# Eurorack_breadboard_PSU_ad.net
KiCad netlist of a schematic drawn in EAGLE
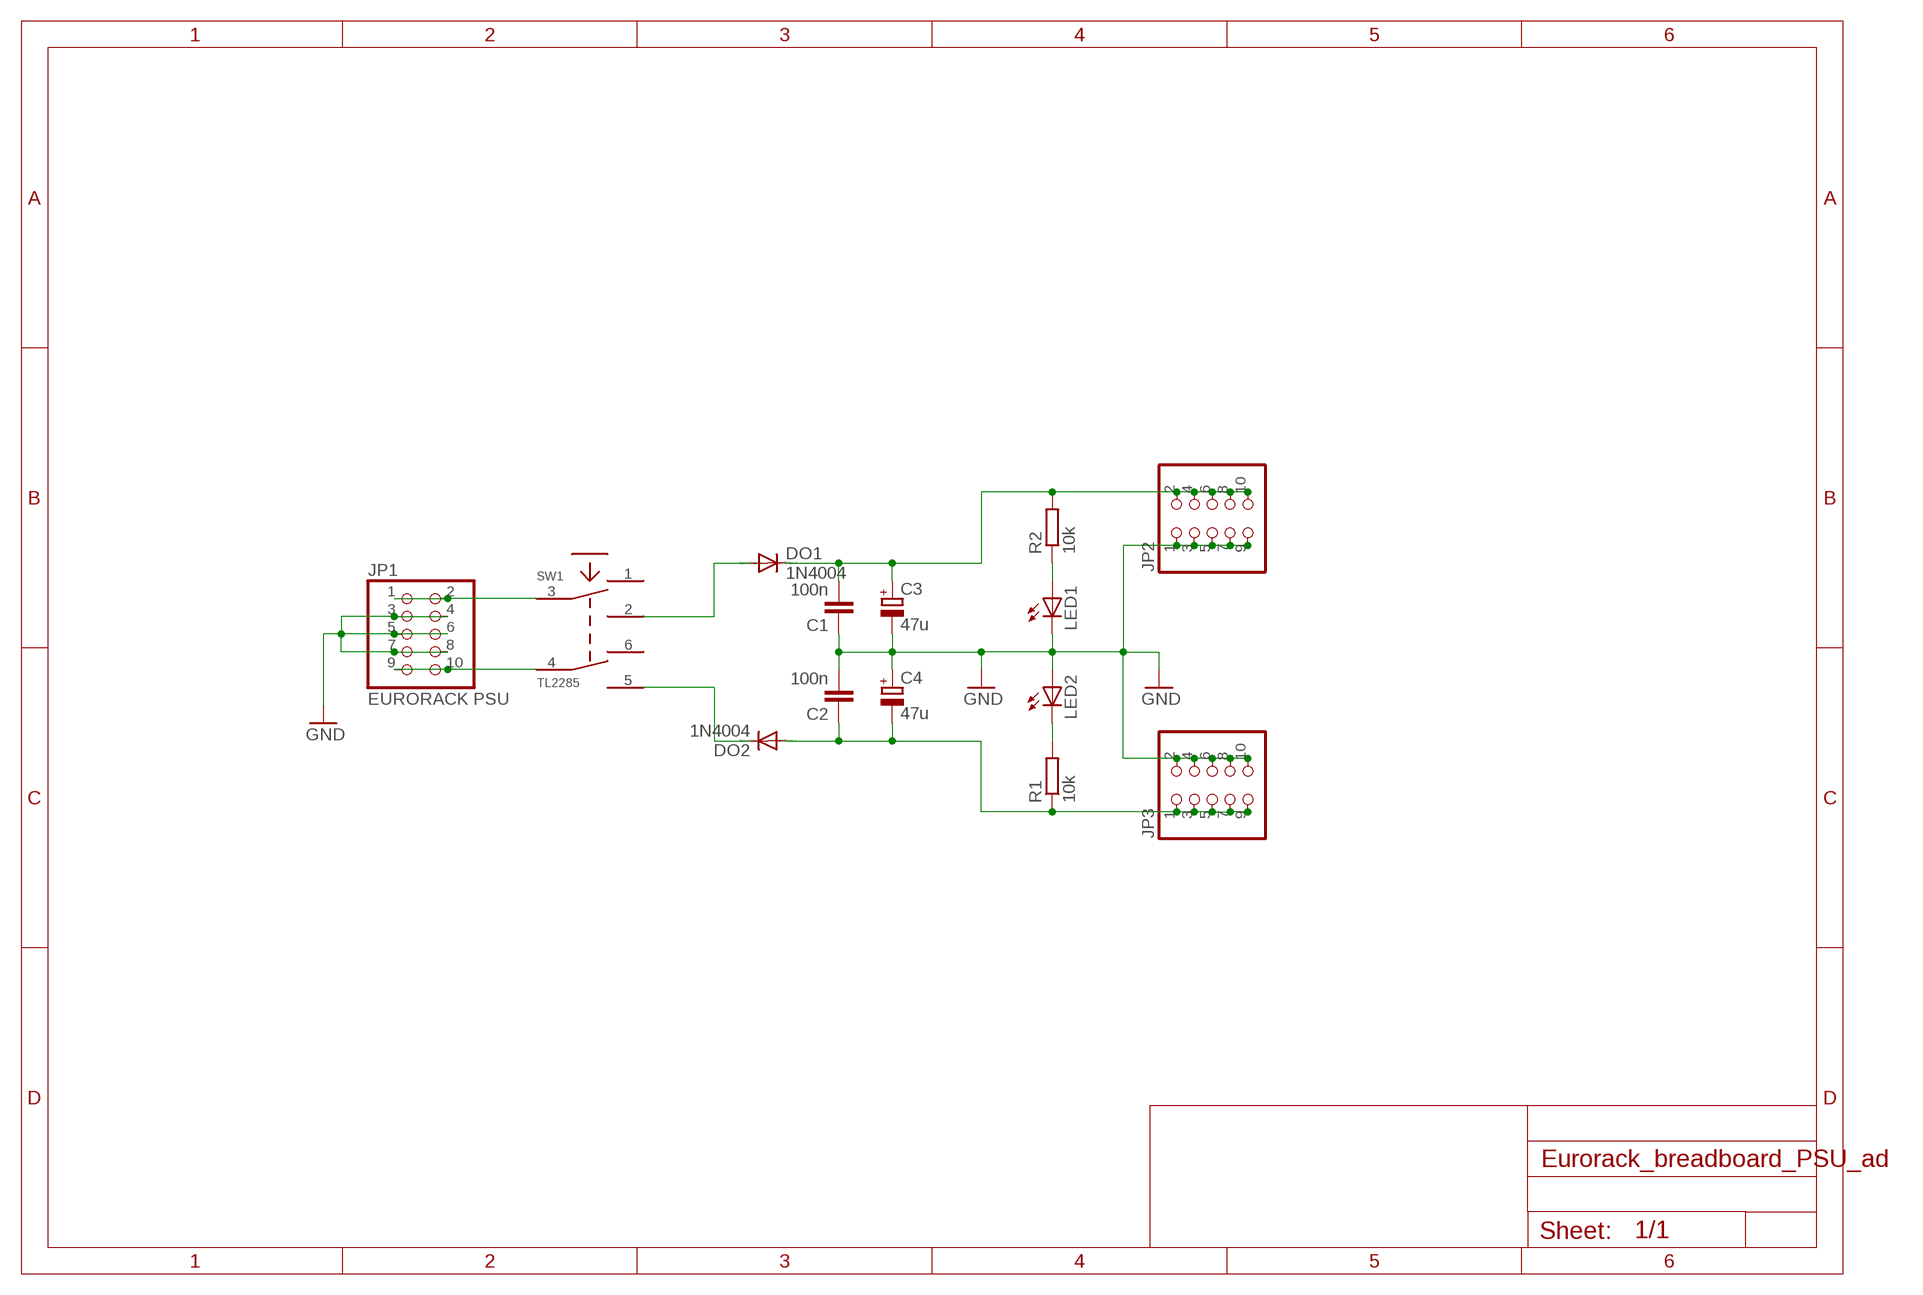
[diagram p0: schematic, sheet 1]

(export (version "E")
  (design (tool "Eeschema 10.0.6"))
  (components
    (comp (ref "C1")
      (value "100n")
      (footprint "eagle-import:C025-025X050")
      (libsource (lib "eagle-import") (part "C-EU025-025X050"))
    )
    (comp (ref "C2")
      (value "100n")
      (footprint "eagle-import:C025-025X050")
      (libsource (lib "eagle-import") (part "C-EU025-025X050"))
    )
    (comp (ref "C3")
      (value "47u")
      (footprint "eagle-import:E2,5-5")
      (libsource (lib "eagle-import") (part "CPOL-EUE2.5-5"))
    )
    (comp (ref "C4")
      (value "47u")
      (footprint "eagle-import:E2,5-5")
      (libsource (lib "eagle-import") (part "CPOL-EUE2.5-5"))
    )
    (comp (ref "DO1")
      (value "1N4004")
      (footprint "eagle-import:DO41-7")
      (libsource (lib "eagle-import") (part "1N4004SMALL"))
    )
    (comp (ref "DO2")
      (value "1N4004")
      (footprint "eagle-import:DO41-7")
      (libsource (lib "eagle-import") (part "1N4004SMALL"))
    )
    (comp (ref "JP1")
      (value "EURORACK PSU")
      (footprint "eagle-import:2X05")
      (libsource (lib "eagle-import") (part "PINHD-2X5"))
    )
    (comp (ref "JP2")
      (value "PINHD-2X5")
      (footprint "eagle-import:2X05")
      (libsource (lib "eagle-import") (part "PINHD-2X5"))
    )
    (comp (ref "JP3")
      (value "PINHD-2X5")
      (footprint "eagle-import:2X05")
      (libsource (lib "eagle-import") (part "PINHD-2X5"))
    )
    (comp (ref "LED1")
      (value "LED3MM")
      (footprint "eagle-import:LED3MM")
      (libsource (lib "eagle-import") (part "LED3MM"))
    )
    (comp (ref "LED2")
      (value "LED3MM")
      (footprint "eagle-import:LED3MM")
      (libsource (lib "eagle-import") (part "LED3MM"))
    )
    (comp (ref "R1")
      (value "10k")
      (footprint "eagle-import:0207_2V")
      (libsource (lib "eagle-import") (part "R-EU_0207/2V"))
    )
    (comp (ref "R2")
      (value "10k")
      (footprint "eagle-import:0207_2V")
      (libsource (lib "eagle-import") (part "R-EU_0207/2V"))
    )
    (comp (ref "SW1")
      (value "TL2285")
      (footprint "eagle-import:TL2285_PCB")
      (libsource (lib "eagle-import") (part "TL2285"))
    )
  )
  (nets
    (net (code "1") (name "GND") (class "Default")
      (node (ref "C1") (pin "1") (pinfunction "1_1") (pintype "passive"))
      (node (ref "C2") (pin "2") (pinfunction "2_2") (pintype "passive"))
      (node (ref "C3") (pin "-") (pinfunction "-_-") (pintype "passive"))
      (node (ref "C4") (pin "+") (pinfunction "+_+") (pintype "passive"))
      (node (ref "JP1") (pin "3") (pinfunction "3_3") (pintype "passive"))
      (node (ref "JP1") (pin "4") (pinfunction "4_4") (pintype "passive"))
      (node (ref "JP1") (pin "5") (pinfunction "5_5") (pintype "passive"))
      (node (ref "JP1") (pin "6") (pinfunction "6_6") (pintype "passive"))
      (node (ref "JP1") (pin "7") (pinfunction "7_7") (pintype "passive"))
      (node (ref "JP1") (pin "8") (pinfunction "8_8") (pintype "passive"))
      (node (ref "JP2") (pin "1") (pinfunction "1_1") (pintype "passive"))
      (node (ref "JP2") (pin "3") (pinfunction "3_3") (pintype "passive"))
      (node (ref "JP2") (pin "5") (pinfunction "5_5") (pintype "passive"))
      (node (ref "JP2") (pin "7") (pinfunction "7_7") (pintype "passive"))
      (node (ref "JP2") (pin "9") (pinfunction "9_9") (pintype "passive"))
      (node (ref "JP3") (pin "10") (pinfunction "10_10") (pintype "passive"))
      (node (ref "JP3") (pin "2") (pinfunction "2_2") (pintype "passive"))
      (node (ref "JP3") (pin "4") (pinfunction "4_4") (pintype "passive"))
      (node (ref "JP3") (pin "6") (pinfunction "6_6") (pintype "passive"))
      (node (ref "JP3") (pin "8") (pinfunction "8_8") (pintype "passive"))
      (node (ref "LED1") (pin "K") (pinfunction "C_K") (pintype "passive"))
      (node (ref "LED2") (pin "A") (pinfunction "A_A") (pintype "passive"))
    )
    (net (code "2") (name "Net-(C1-Pad2)") (class "Default")
      (node (ref "C1") (pin "2") (pinfunction "2_2") (pintype "passive"))
      (node (ref "C3") (pin "+") (pinfunction "+_+") (pintype "passive"))
      (node (ref "DO1") (pin "C") (pinfunction "C_C") (pintype "passive"))
      (node (ref "JP2") (pin "10") (pinfunction "10_10") (pintype "passive"))
      (node (ref "JP2") (pin "2") (pinfunction "2_2") (pintype "passive"))
      (node (ref "JP2") (pin "4") (pinfunction "4_4") (pintype "passive"))
      (node (ref "JP2") (pin "6") (pinfunction "6_6") (pintype "passive"))
      (node (ref "JP2") (pin "8") (pinfunction "8_8") (pintype "passive"))
      (node (ref "R2") (pin "2") (pinfunction "2_2") (pintype "passive"))
    )
    (net (code "3") (name "Net-(C2-Pad1)") (class "Default")
      (node (ref "C2") (pin "1") (pinfunction "1_1") (pintype "passive"))
      (node (ref "C4") (pin "-") (pinfunction "-_-") (pintype "passive"))
      (node (ref "DO2") (pin "A") (pinfunction "A_A") (pintype "passive"))
      (node (ref "JP3") (pin "1") (pinfunction "1_1") (pintype "passive"))
      (node (ref "JP3") (pin "3") (pinfunction "3_3") (pintype "passive"))
      (node (ref "JP3") (pin "5") (pinfunction "5_5") (pintype "passive"))
      (node (ref "JP3") (pin "7") (pinfunction "7_7") (pintype "passive"))
      (node (ref "JP3") (pin "9") (pinfunction "9_9") (pintype "passive"))
      (node (ref "R1") (pin "1") (pinfunction "1_1") (pintype "passive"))
    )
    (net (code "4") (name "Net-(LED1-PadA)") (class "Default")
      (node (ref "LED1") (pin "A") (pinfunction "A_A") (pintype "passive"))
      (node (ref "R2") (pin "1") (pinfunction "1_1") (pintype "passive"))
    )
    (net (code "5") (name "Net-(LED2-C)") (class "Default")
      (node (ref "LED2") (pin "K") (pinfunction "C_K") (pintype "passive"))
      (node (ref "R1") (pin "2") (pinfunction "2_2") (pintype "passive"))
    )
    (net (code "6") (name "Net-(SW1-P2)") (class "Default")
      (node (ref "DO1") (pin "A") (pinfunction "A_A") (pintype "passive"))
      (node (ref "SW1") (pin "2") (pinfunction "P2_2") (pintype "bidirectional"))
    )
    (net (code "7") (name "Net-(SW1-P3)") (class "Default")
      (node (ref "JP1") (pin "1") (pinfunction "1_1") (pintype "passive"))
      (node (ref "JP1") (pin "2") (pinfunction "2_2") (pintype "passive"))
      (node (ref "SW1") (pin "3") (pinfunction "P3_3") (pintype "bidirectional"))
    )
    (net (code "8") (name "Net-(SW1-P4)") (class "Default")
      (node (ref "JP1") (pin "10") (pinfunction "10_10") (pintype "passive"))
      (node (ref "JP1") (pin "9") (pinfunction "9_9") (pintype "passive"))
      (node (ref "SW1") (pin "4") (pinfunction "P4_4") (pintype "bidirectional"))
    )
    (net (code "9") (name "Net-(SW1-P5)") (class "Default")
      (node (ref "DO2") (pin "C") (pinfunction "C_C") (pintype "passive"))
      (node (ref "SW1") (pin "5") (pinfunction "P5_5") (pintype "bidirectional"))
    )
    (net (code "10") (name "unconnected-(SW1-P1-Pad1)") (class "Default")
      (node (ref "SW1") (pin "1") (pinfunction "P1_1") (pintype "bidirectional"))
    )
    (net (code "11") (name "unconnected-(SW1-P6-Pad6)") (class "Default")
      (node (ref "SW1") (pin "6") (pinfunction "P6_6") (pintype "bidirectional"))
    )
  )
)
